# ONLY_HBRIDGE_v4.net
KiCad netlist of a schematic drawn in EAGLE
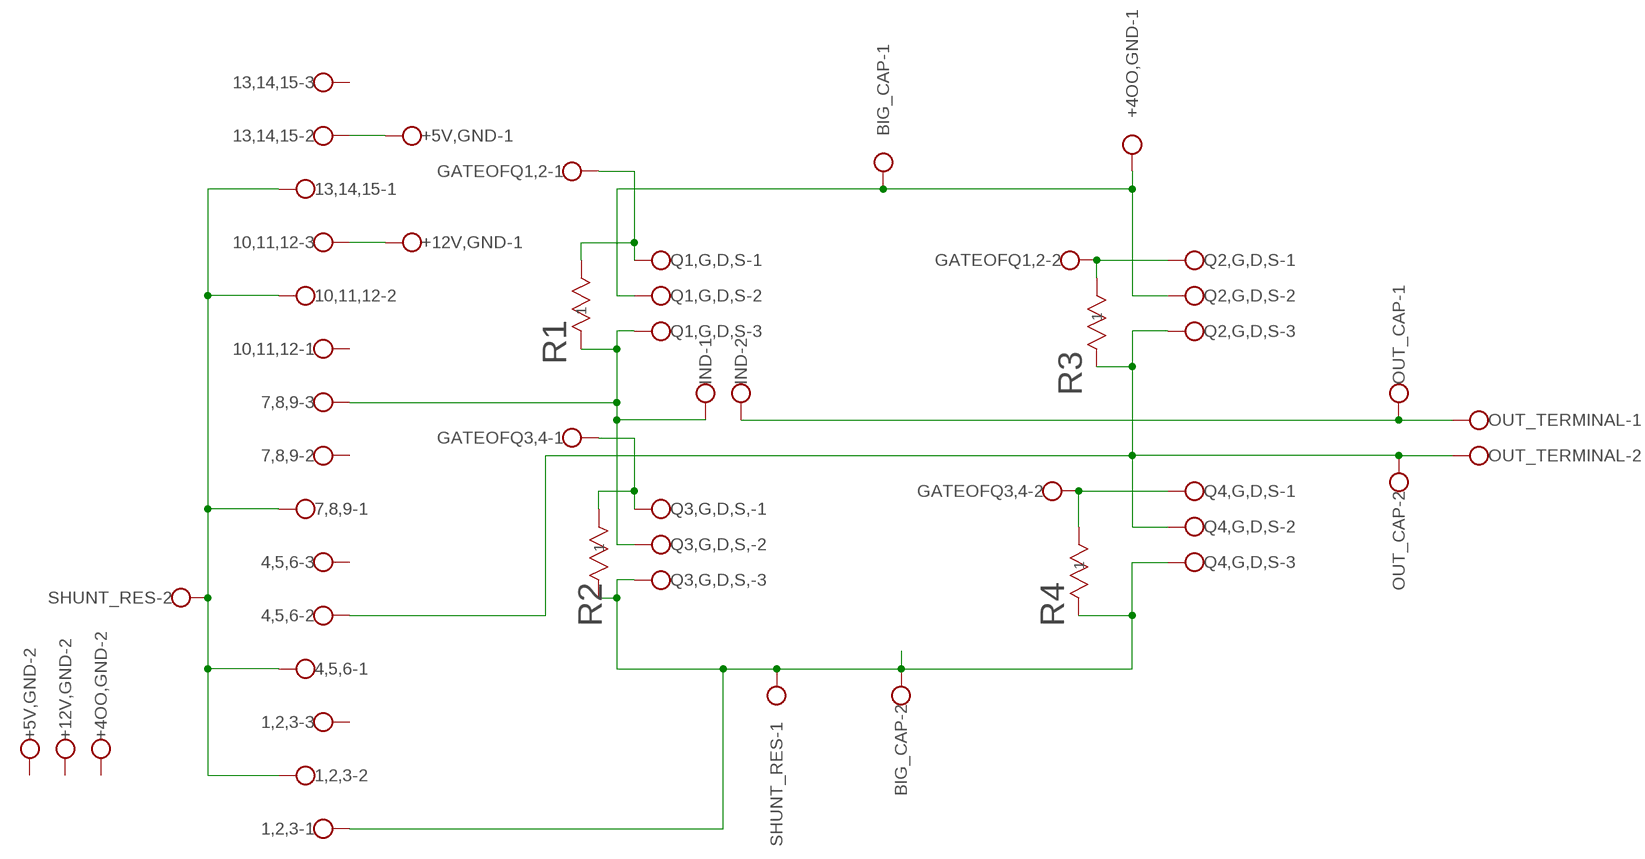
[diagram p0: schematic, sheet 1]

(export (version "E")
  (design (tool "Eeschema 10.0.6"))
  (components
    (comp (ref "+4OO,GND")
      (value "W237-02P")
      (footprint "eagle-import:W237-132")
      (libsource (lib "eagle-import") (part "W237-02P"))
    )
    (comp (ref "+5V,GND")
      (value "W237-02P")
      (footprint "eagle-import:W237-132")
      (libsource (lib "eagle-import") (part "W237-02P"))
    )
    (comp (ref "+12V,GND")
      (value "W237-02P")
      (footprint "eagle-import:W237-132")
      (libsource (lib "eagle-import") (part "W237-02P"))
    )
    (comp (ref "1,2,3")
      (value "W237-03P")
      (footprint "eagle-import:W237-133")
      (libsource (lib "eagle-import") (part "W237-03P"))
    )
    (comp (ref "4,5,6")
      (value "W237-03P")
      (footprint "eagle-import:W237-133")
      (libsource (lib "eagle-import") (part "W237-03P"))
    )
    (comp (ref "7,8,9")
      (value "W237-03P")
      (footprint "eagle-import:W237-133")
      (libsource (lib "eagle-import") (part "W237-03P"))
    )
    (comp (ref "10,11,12")
      (value "W237-03P")
      (footprint "eagle-import:W237-133")
      (libsource (lib "eagle-import") (part "W237-03P"))
    )
    (comp (ref "13,14,15")
      (value "W237-03P")
      (footprint "eagle-import:W237-133")
      (libsource (lib "eagle-import") (part "W237-03P"))
    )
    (comp (ref "BIG_CAP")
      (value "W237-02P")
      (footprint "eagle-import:W237-132")
      (libsource (lib "eagle-import") (part "W237-02P"))
    )
    (comp (ref "GATEOFQ1,2")
      (value "W237-02P")
      (footprint "eagle-import:W237-132")
      (libsource (lib "eagle-import") (part "W237-02P"))
    )
    (comp (ref "GATEOFQ3,4")
      (value "W237-02P")
      (footprint "eagle-import:W237-132")
      (libsource (lib "eagle-import") (part "W237-02P"))
    )
    (comp (ref "IND")
      (value "W237-02P")
      (footprint "eagle-import:W237-132")
      (libsource (lib "eagle-import") (part "W237-02P"))
    )
    (comp (ref "OUT_CAP")
      (value "W237-02P")
      (footprint "eagle-import:W237-132")
      (libsource (lib "eagle-import") (part "W237-02P"))
    )
    (comp (ref "OUT_TERMINAL")
      (value "W237-02P")
      (footprint "eagle-import:W237-132")
      (libsource (lib "eagle-import") (part "W237-02P"))
    )
    (comp (ref "Q1,G,D,S")
      (value "W237-03P")
      (footprint "eagle-import:W237-133")
      (libsource (lib "eagle-import") (part "W237-03P"))
    )
    (comp (ref "Q2,G,D,S")
      (value "W237-03P")
      (footprint "eagle-import:W237-133")
      (libsource (lib "eagle-import") (part "W237-03P"))
    )
    (comp (ref "Q3,G,D,S,")
      (value "W237-03P")
      (footprint "eagle-import:W237-133")
      (libsource (lib "eagle-import") (part "W237-03P"))
    )
    (comp (ref "Q4,G,D,S")
      (value "W237-03P")
      (footprint "eagle-import:W237-133")
      (libsource (lib "eagle-import") (part "W237-03P"))
    )
    (comp (ref "R1")
      (value "CF14JT10K0STA_CF14_STP")
      (footprint "eagle-import:STA_CF14_STP")
      (fields
        (field (name "MANUFACTURER_PART_NUMBER") "CF14JT10K0")
        (field (name "COPYRIGHT") "Copyright (C) 2024 Ultra Librarian. All rights reserved.")
      )
      (libsource (lib "eagle-import") (part "CF14JT10K0STA_CF14_STP"))
    )
    (comp (ref "R2")
      (value "CF14JT10K0STA_CF14_STP")
      (footprint "eagle-import:STA_CF14_STP")
      (fields
        (field (name "MANUFACTURER_PART_NUMBER") "CF14JT10K0")
        (field (name "COPYRIGHT") "Copyright (C) 2024 Ultra Librarian. All rights reserved.")
      )
      (libsource (lib "eagle-import") (part "CF14JT10K0STA_CF14_STP"))
    )
    (comp (ref "R3")
      (value "CF14JT10K0STA_CF14_STP")
      (footprint "eagle-import:STA_CF14_STP")
      (fields
        (field (name "MANUFACTURER_PART_NUMBER") "CF14JT10K0")
        (field (name "COPYRIGHT") "Copyright (C) 2024 Ultra Librarian. All rights reserved.")
      )
      (libsource (lib "eagle-import") (part "CF14JT10K0STA_CF14_STP"))
    )
    (comp (ref "R4")
      (value "CF14JT10K0STA_CF14_STP")
      (footprint "eagle-import:STA_CF14_STP")
      (fields
        (field (name "MANUFACTURER_PART_NUMBER") "CF14JT10K0")
        (field (name "COPYRIGHT") "Copyright (C) 2024 Ultra Librarian. All rights reserved.")
      )
      (libsource (lib "eagle-import") (part "CF14JT10K0STA_CF14_STP"))
    )
    (comp (ref "SHUNT_RES")
      (value "W237-02P")
      (footprint "eagle-import:W237-132")
      (libsource (lib "eagle-import") (part "W237-02P"))
    )
  )
  (nets
    (net (code "1") (name "Net-(+4OO,GNDA-KL)") (class "Default")
      (node (ref "+4OO,GND") (pin "1") (pinfunction "KL_1") (pintype "passive"))
      (node (ref "BIG_CAP") (pin "1") (pinfunction "KL_1") (pintype "passive"))
      (node (ref "Q1,G,D,S") (pin "2") (pinfunction "KL_2") (pintype "passive"))
      (node (ref "Q2,G,D,S") (pin "2") (pinfunction "KL_2") (pintype "passive"))
    )
    (net (code "2") (name "Net-(+5V,GNDA-KL)") (class "Default")
      (node (ref "+5V,GND") (pin "1") (pinfunction "KL_1") (pintype "passive"))
      (node (ref "13,14,15") (pin "2") (pinfunction "KL_2") (pintype "passive"))
    )
    (net (code "3") (name "Net-(+12V,GNDA-KL)") (class "Default")
      (node (ref "+12V,GND") (pin "1") (pinfunction "KL_1") (pintype "passive"))
      (node (ref "10,11,12") (pin "3") (pinfunction "KL_3") (pintype "passive"))
    )
    (net (code "4") (name "Net-(1,2,3A-KL)") (class "Default")
      (node (ref "1,2,3") (pin "1") (pinfunction "KL_1") (pintype "passive"))
      (node (ref "BIG_CAP") (pin "2") (pinfunction "KL_2") (pintype "passive"))
      (node (ref "Q3,G,D,S,") (pin "3") (pinfunction "KL_3") (pintype "passive"))
      (node (ref "Q4,G,D,S") (pin "3") (pinfunction "KL_3") (pintype "passive"))
      (node (ref "R2") (pin "2") (pinfunction "2_2") (pintype "passive"))
      (node (ref "R4") (pin "2") (pinfunction "2_2") (pintype "passive"))
      (node (ref "SHUNT_RES") (pin "1") (pinfunction "KL_1") (pintype "passive"))
    )
    (net (code "5") (name "Net-(1,2,3B-KL)") (class "Default")
      (node (ref "1,2,3") (pin "2") (pinfunction "KL_2") (pintype "passive"))
      (node (ref "10,11,12") (pin "2") (pinfunction "KL_2") (pintype "passive"))
      (node (ref "13,14,15") (pin "1") (pinfunction "KL_1") (pintype "passive"))
      (node (ref "4,5,6") (pin "1") (pinfunction "KL_1") (pintype "passive"))
      (node (ref "7,8,9") (pin "1") (pinfunction "KL_1") (pintype "passive"))
      (node (ref "SHUNT_RES") (pin "2") (pinfunction "KL_2") (pintype "passive"))
    )
    (net (code "6") (name "Net-(4,5,6B-KL)") (class "Default")
      (node (ref "4,5,6") (pin "2") (pinfunction "KL_2") (pintype "passive"))
      (node (ref "OUT_CAP") (pin "2") (pinfunction "KL_2") (pintype "passive"))
      (node (ref "OUT_TERMINAL") (pin "2") (pinfunction "KL_2") (pintype "passive"))
      (node (ref "Q2,G,D,S") (pin "3") (pinfunction "KL_3") (pintype "passive"))
      (node (ref "Q4,G,D,S") (pin "2") (pinfunction "KL_2") (pintype "passive"))
      (node (ref "R3") (pin "2") (pinfunction "2_2") (pintype "passive"))
    )
    (net (code "7") (name "Net-(7,8,9C-KL)") (class "Default")
      (node (ref "7,8,9") (pin "3") (pinfunction "KL_3") (pintype "passive"))
      (node (ref "IND") (pin "1") (pinfunction "KL_1") (pintype "passive"))
      (node (ref "Q1,G,D,S") (pin "3") (pinfunction "KL_3") (pintype "passive"))
      (node (ref "Q3,G,D,S,") (pin "2") (pinfunction "KL_2") (pintype "passive"))
      (node (ref "R1") (pin "1") (pinfunction "1_1") (pintype "passive"))
    )
    (net (code "8") (name "Net-(GATEOFQ1,2A-KL)") (class "Default")
      (node (ref "GATEOFQ1,2") (pin "1") (pinfunction "KL_1") (pintype "passive"))
      (node (ref "Q1,G,D,S") (pin "1") (pinfunction "KL_1") (pintype "passive"))
      (node (ref "R1") (pin "2") (pinfunction "2_2") (pintype "passive"))
    )
    (net (code "9") (name "Net-(GATEOFQ1,2B-KL)") (class "Default")
      (node (ref "GATEOFQ1,2") (pin "2") (pinfunction "KL_2") (pintype "passive"))
      (node (ref "Q2,G,D,S") (pin "1") (pinfunction "KL_1") (pintype "passive"))
      (node (ref "R3") (pin "1") (pinfunction "1_1") (pintype "passive"))
    )
    (net (code "10") (name "Net-(GATEOFQ3,4A-KL)") (class "Default")
      (node (ref "GATEOFQ3,4") (pin "1") (pinfunction "KL_1") (pintype "passive"))
      (node (ref "Q3,G,D,S,") (pin "1") (pinfunction "KL_1") (pintype "passive"))
      (node (ref "R2") (pin "1") (pinfunction "1_1") (pintype "passive"))
    )
    (net (code "11") (name "Net-(GATEOFQ3,4B-KL)") (class "Default")
      (node (ref "GATEOFQ3,4") (pin "2") (pinfunction "KL_2") (pintype "passive"))
      (node (ref "Q4,G,D,S") (pin "1") (pinfunction "KL_1") (pintype "passive"))
      (node (ref "R4") (pin "1") (pinfunction "1_1") (pintype "passive"))
    )
    (net (code "12") (name "Net-(INDB-KL)") (class "Default")
      (node (ref "IND") (pin "2") (pinfunction "KL_2") (pintype "passive"))
      (node (ref "OUT_CAP") (pin "1") (pinfunction "KL_1") (pintype "passive"))
      (node (ref "OUT_TERMINAL") (pin "1") (pinfunction "KL_1") (pintype "passive"))
    )
    (net (code "13") (name "unconnected-(+4OO,GNDB-KL-Pad2)") (class "Default")
      (node (ref "+4OO,GND") (pin "2") (pinfunction "KL_2") (pintype "passive"))
    )
    (net (code "14") (name "unconnected-(+5V,GNDB-KL-Pad2)") (class "Default")
      (node (ref "+5V,GND") (pin "2") (pinfunction "KL_2") (pintype "passive"))
    )
    (net (code "15") (name "unconnected-(+12V,GNDB-KL-Pad2)") (class "Default")
      (node (ref "+12V,GND") (pin "2") (pinfunction "KL_2") (pintype "passive"))
    )
    (net (code "16") (name "unconnected-(1,2,3C-KL-Pad3)") (class "Default")
      (node (ref "1,2,3") (pin "3") (pinfunction "KL_3") (pintype "passive"))
    )
    (net (code "17") (name "unconnected-(4,5,6C-KL-Pad3)") (class "Default")
      (node (ref "4,5,6") (pin "3") (pinfunction "KL_3") (pintype "passive"))
    )
    (net (code "18") (name "unconnected-(7,8,9B-KL-Pad2)") (class "Default")
      (node (ref "7,8,9") (pin "2") (pinfunction "KL_2") (pintype "passive"))
    )
    (net (code "19") (name "unconnected-(10,11,12A-KL-Pad1)") (class "Default")
      (node (ref "10,11,12") (pin "1") (pinfunction "KL_1") (pintype "passive"))
    )
    (net (code "20") (name "unconnected-(13,14,15C-KL-Pad3)") (class "Default")
      (node (ref "13,14,15") (pin "3") (pinfunction "KL_3") (pintype "passive"))
    )
  )
)
